# controller_v5.net
KiCad netlist of a schematic drawn in EAGLE
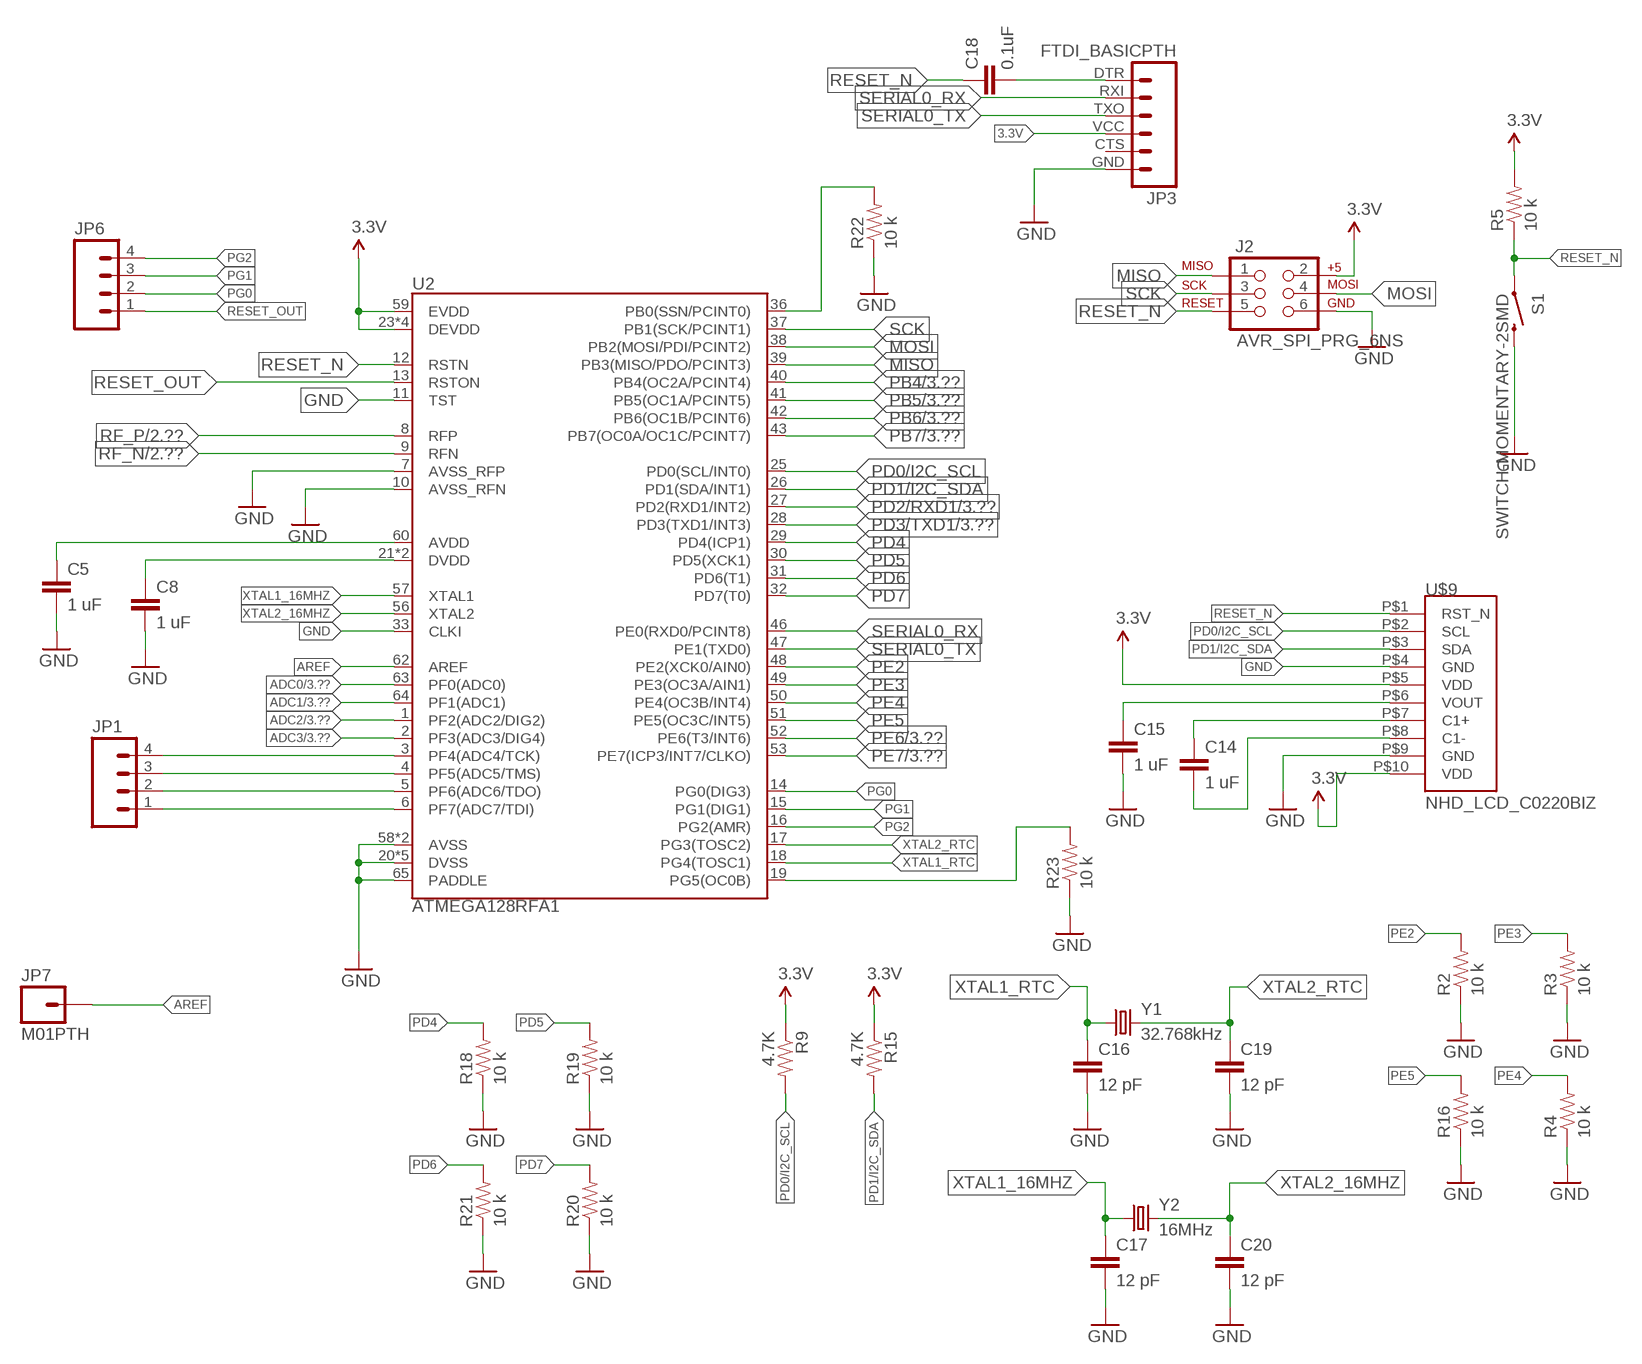
[diagram p0: schematic, sheet 1]
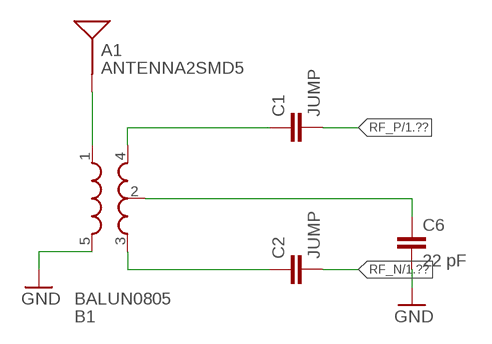
[diagram p1: schematic, sheet 2]
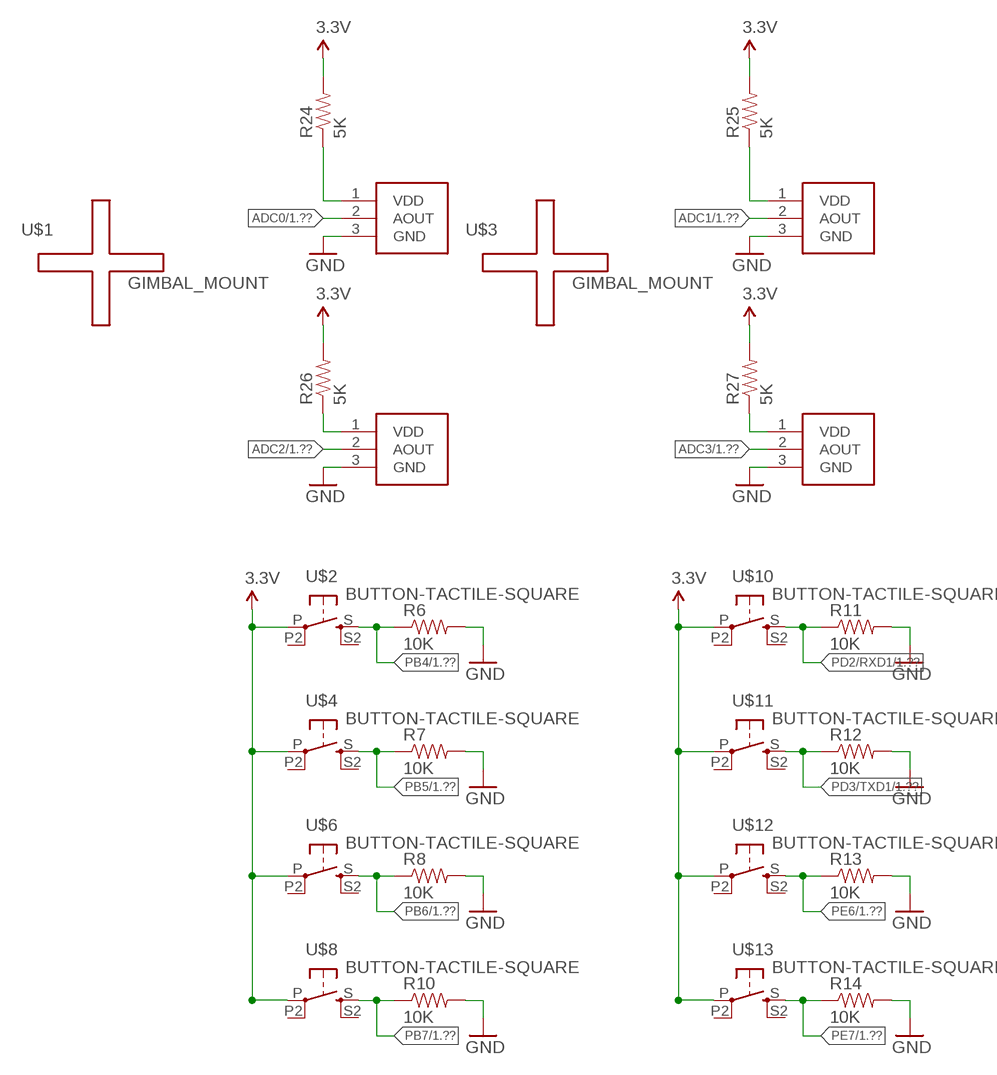
[diagram p2: schematic, sheet 3]
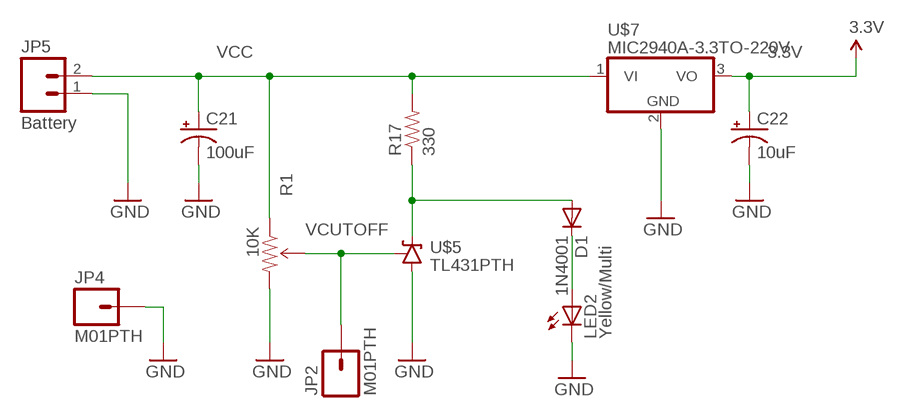
[diagram p3: schematic, sheet 4]

(export (version "E")
  (design (tool "Eeschema 10.0.6"))
  (components
    (comp (ref "C21")
      (value "100uF")
      (footprint "eagle-import:E3,5-8")
      (libsource (lib "eagle-import") (part "CPOL-USE3.5-8"))
    )
    (comp (ref "C22")
      (value "10uF")
      (footprint "eagle-import:E2,5-5")
      (libsource (lib "eagle-import") (part "CPOL-USE2.5-5"))
    )
    (comp (ref "D1")
      (value "1N4001")
      (footprint "eagle-import:DO41-10")
      (libsource (lib "eagle-import") (part "1N4004"))
    )
    (comp (ref "JP2")
      (value "M01PTH")
      (footprint "eagle-import:1X01")
      (libsource (lib "eagle-import") (part "SparkFun_M01PTH"))
    )
    (comp (ref "JP4")
      (value "M01PTH")
      (footprint "eagle-import:1X01")
      (libsource (lib "eagle-import") (part "SparkFun_M01PTH"))
    )
    (comp (ref "JP5")
      (value "Battery")
      (footprint "eagle-import:1X02")
      (libsource (lib "eagle-import") (part "M02PTH"))
    )
    (comp (ref "LED2")
      (value "Yellow/Multi")
      (footprint "eagle-import:LED5MM")
      (libsource (lib "eagle-import") (part "LED5MM"))
    )
    (comp (ref "R1")
      (value "10K")
      (footprint "eagle-import:3386U")
      (fields (field (name "CREATOR") "Brandon") (field (name "REVIEWER1") "Chris"))
      (libsource (lib "eagle-import") (part "TRIMPOT-PTH-KNOB"))
    )
    (comp (ref "R17")
      (value "330")
      (footprint "eagle-import:AXIAL-0.3")
      (libsource (lib "eagle-import") (part "SparkFun_RESISTORAXIAL-0.3"))
    )
    (comp (ref "U$5")
      (value "TL431PTH")
      (footprint "eagle-import:TO-92")
      (libsource (lib "eagle-import") (part "TL431PTH"))
    )
    (comp (ref "U$7")
      (value "MIC2940A-3.3TO-220V")
      (footprint "eagle-import:TO-220V")
      (libsource (lib "eagle-import") (part "MIC2940A-3.3TO-220V"))
    )
    (comp (ref "C5")
      (value "1 uF")
      (footprint "eagle-import:0805")
      (libsource (lib "eagle-import") (part "CAP0805"))
    )
    (comp (ref "C8")
      (value "1 uF")
      (footprint "eagle-import:0805")
      (libsource (lib "eagle-import") (part "CAP0805"))
    )
    (comp (ref "C14")
      (value "1 uF")
      (footprint "eagle-import:0805")
      (libsource (lib "eagle-import") (part "CAP0805"))
    )
    (comp (ref "C15")
      (value "1 uF")
      (footprint "eagle-import:0805")
      (libsource (lib "eagle-import") (part "CAP0805"))
    )
    (comp (ref "C16")
      (value "12 pF")
      (footprint "eagle-import:0805")
      (libsource (lib "eagle-import") (part "CAP0805"))
    )
    (comp (ref "C17")
      (value "12 pF")
      (footprint "eagle-import:0805")
      (libsource (lib "eagle-import") (part "CAP0805"))
    )
    (comp (ref "C18")
      (value "0.1uF")
      (footprint "eagle-import:0805")
      (libsource (lib "eagle-import") (part "CAP0805"))
    )
    (comp (ref "C19")
      (value "12 pF")
      (footprint "eagle-import:0805")
      (libsource (lib "eagle-import") (part "CAP0805"))
    )
    (comp (ref "C20")
      (value "12 pF")
      (footprint "eagle-import:0805")
      (libsource (lib "eagle-import") (part "CAP0805"))
    )
    (comp (ref "J2")
      (value "AVR_SPI_PRG_6NS")
      (footprint "eagle-import:2X3-NS")
      (libsource (lib "eagle-import") (part "AVR_SPI_PRG_6NS"))
    )
    (comp (ref "JP1")
      (value "M04PTH")
      (footprint "eagle-import:1X04")
      (libsource (lib "eagle-import") (part "M04PTH"))
    )
    (comp (ref "JP3")
      (value "FTDI_BASICPTH")
      (footprint "eagle-import:FTDI_BASIC")
      (libsource (lib "eagle-import") (part "FTDI_BASICPTH"))
    )
    (comp (ref "JP6")
      (value "M04PTH")
      (footprint "eagle-import:1X04")
      (libsource (lib "eagle-import") (part "M04PTH"))
    )
    (comp (ref "JP7")
      (value "M01PTH")
      (footprint "eagle-import:1X01")
      (libsource (lib "eagle-import") (part "M01PTH"))
    )
    (comp (ref "R2")
      (value "10 k")
      (footprint "eagle-import:0805")
      (libsource (lib "eagle-import") (part "RESISTOR0805-RES"))
    )
    (comp (ref "R3")
      (value "10 k")
      (footprint "eagle-import:0805")
      (libsource (lib "eagle-import") (part "RESISTOR0805-RES"))
    )
    (comp (ref "R4")
      (value "10 k")
      (footprint "eagle-import:0805")
      (libsource (lib "eagle-import") (part "RESISTOR0805-RES"))
    )
    (comp (ref "R5")
      (value "10 k")
      (footprint "eagle-import:0805")
      (libsource (lib "eagle-import") (part "RESISTOR0805-RES"))
    )
    (comp (ref "R9")
      (value "4.7K")
      (footprint "eagle-import:0805")
      (libsource (lib "eagle-import") (part "RESISTOR0805-RES"))
    )
    (comp (ref "R15")
      (value "4.7K")
      (footprint "eagle-import:0805")
      (libsource (lib "eagle-import") (part "RESISTOR0805-RES"))
    )
    (comp (ref "R16")
      (value "10 k")
      (footprint "eagle-import:0805")
      (libsource (lib "eagle-import") (part "RESISTOR0805-RES"))
    )
    (comp (ref "R18")
      (value "10 k")
      (footprint "eagle-import:0805")
      (libsource (lib "eagle-import") (part "RESISTOR0805-RES"))
    )
    (comp (ref "R19")
      (value "10 k")
      (footprint "eagle-import:0805")
      (libsource (lib "eagle-import") (part "RESISTOR0805-RES"))
    )
    (comp (ref "R20")
      (value "10 k")
      (footprint "eagle-import:0805")
      (libsource (lib "eagle-import") (part "RESISTOR0805-RES"))
    )
    (comp (ref "R21")
      (value "10 k")
      (footprint "eagle-import:0805")
      (libsource (lib "eagle-import") (part "RESISTOR0805-RES"))
    )
    (comp (ref "R22")
      (value "10 k")
      (footprint "eagle-import:0805")
      (libsource (lib "eagle-import") (part "RESISTOR0805-RES"))
    )
    (comp (ref "R23")
      (value "10 k")
      (footprint "eagle-import:0805")
      (libsource (lib "eagle-import") (part "RESISTOR0805-RES"))
    )
    (comp (ref "S1")
      (value "SWITCH-MOMENTARY-2SMD")
      (footprint "eagle-import:TACTILE_SWITCH_SMD")
      (libsource (lib "eagle-import") (part "SWITCH-MOMENTARY-2SMD"))
    )
    (comp (ref "U$9")
      (value "NHD_LCD_C0220BIZ")
      (footprint "eagle-import:1X08-2MMPTH-LCD")
      (libsource (lib "eagle-import") (part "NHD_LCD_C0220BIZ"))
    )
    (comp (ref "U2")
      (value "ATMEGA128RFA1")
      (footprint "eagle-import:QFN-64")
      (libsource (lib "eagle-import") (part "ATMEGA128RFA1"))
    )
    (comp (ref "Y1")
      (value "32.768kHz")
      (footprint "eagle-import:CRYSTAL-32KHZ-SMD")
      (libsource (lib "eagle-import") (part "CRYSTAL32-SMD"))
    )
    (comp (ref "Y2")
      (value "16MHz")
      (footprint "eagle-import:CRYSTAL-SMD-5X3")
      (libsource (lib "eagle-import") (part "CRYSTAL5X3"))
    )
    (comp (ref "J3")
      (value "GIMBAL_3PIN")
      (footprint "eagle-import:JST-3-PTH")
      (libsource (lib "eagle-import") (part "GIMBAL_3PIN"))
    )
    (comp (ref "J4")
      (value "GIMBAL_3PIN")
      (footprint "eagle-import:JST-3-PTH")
      (libsource (lib "eagle-import") (part "GIMBAL_3PIN"))
    )
    (comp (ref "J5")
      (value "GIMBAL_3PIN")
      (footprint "eagle-import:JST-3-PTH")
      (libsource (lib "eagle-import") (part "GIMBAL_3PIN"))
    )
    (comp (ref "J6")
      (value "GIMBAL_3PIN")
      (footprint "eagle-import:JST-3-PTH")
      (libsource (lib "eagle-import") (part "GIMBAL_3PIN"))
    )
    (comp (ref "R6")
      (value "10K")
      (footprint "eagle-import:0805")
      (libsource (lib "eagle-import") (part "RESISTOR0805-RES"))
    )
    (comp (ref "R7")
      (value "10K")
      (footprint "eagle-import:0805")
      (libsource (lib "eagle-import") (part "RESISTOR0805-RES"))
    )
    (comp (ref "R8")
      (value "10K")
      (footprint "eagle-import:0805")
      (libsource (lib "eagle-import") (part "RESISTOR0805-RES"))
    )
    (comp (ref "R10")
      (value "10K")
      (footprint "eagle-import:0805")
      (libsource (lib "eagle-import") (part "RESISTOR0805-RES"))
    )
    (comp (ref "R11")
      (value "10K")
      (footprint "eagle-import:0805")
      (libsource (lib "eagle-import") (part "RESISTOR0805-RES"))
    )
    (comp (ref "R12")
      (value "10K")
      (footprint "eagle-import:0805")
      (libsource (lib "eagle-import") (part "RESISTOR0805-RES"))
    )
    (comp (ref "R13")
      (value "10K")
      (footprint "eagle-import:0805")
      (libsource (lib "eagle-import") (part "RESISTOR0805-RES"))
    )
    (comp (ref "R14")
      (value "10K")
      (footprint "eagle-import:0805")
      (libsource (lib "eagle-import") (part "RESISTOR0805-RES"))
    )
    (comp (ref "R24")
      (value "5K")
      (footprint "eagle-import:0805")
      (libsource (lib "eagle-import") (part "RESISTOR0805-RES"))
    )
    (comp (ref "R25")
      (value "5K")
      (footprint "eagle-import:0805")
      (libsource (lib "eagle-import") (part "RESISTOR0805-RES"))
    )
    (comp (ref "R26")
      (value "5K")
      (footprint "eagle-import:0805")
      (libsource (lib "eagle-import") (part "RESISTOR0805-RES"))
    )
    (comp (ref "R27")
      (value "5K")
      (footprint "eagle-import:0805")
      (libsource (lib "eagle-import") (part "RESISTOR0805-RES"))
    )
    (comp (ref "U$1")
      (value "GIMBAL_MOUNT")
      (footprint "eagle-import:GIMBAL_FOOTPRINT")
      (libsource (lib "eagle-import") (part "GIMBAL_MOUNT"))
    )
    (comp (ref "U$2")
      (value "BUTTON-TACTILE-SQUARE")
      (footprint "eagle-import:BUTTON-TACTILE-SQUARE-ADAFRUIT1010")
      (libsource (lib "eagle-import") (part "BUTTON-TACTILE-SQUARE"))
    )
    (comp (ref "U$3")
      (value "GIMBAL_MOUNT")
      (footprint "eagle-import:GIMBAL_FOOTPRINT")
      (libsource (lib "eagle-import") (part "GIMBAL_MOUNT"))
    )
    (comp (ref "U$4")
      (value "BUTTON-TACTILE-SQUARE")
      (footprint "eagle-import:BUTTON-TACTILE-SQUARE-ADAFRUIT1010")
      (libsource (lib "eagle-import") (part "BUTTON-TACTILE-SQUARE"))
    )
    (comp (ref "U$6")
      (value "BUTTON-TACTILE-SQUARE")
      (footprint "eagle-import:BUTTON-TACTILE-SQUARE-ADAFRUIT1010")
      (libsource (lib "eagle-import") (part "BUTTON-TACTILE-SQUARE"))
    )
    (comp (ref "U$8")
      (value "BUTTON-TACTILE-SQUARE")
      (footprint "eagle-import:BUTTON-TACTILE-SQUARE-ADAFRUIT1010")
      (libsource (lib "eagle-import") (part "BUTTON-TACTILE-SQUARE"))
    )
    (comp (ref "U$10")
      (value "BUTTON-TACTILE-SQUARE")
      (footprint "eagle-import:BUTTON-TACTILE-SQUARE-ADAFRUIT1010")
      (libsource (lib "eagle-import") (part "BUTTON-TACTILE-SQUARE"))
    )
    (comp (ref "U$11")
      (value "BUTTON-TACTILE-SQUARE")
      (footprint "eagle-import:BUTTON-TACTILE-SQUARE-ADAFRUIT1010")
      (libsource (lib "eagle-import") (part "BUTTON-TACTILE-SQUARE"))
    )
    (comp (ref "U$12")
      (value "BUTTON-TACTILE-SQUARE")
      (footprint "eagle-import:BUTTON-TACTILE-SQUARE-ADAFRUIT1010")
      (libsource (lib "eagle-import") (part "BUTTON-TACTILE-SQUARE"))
    )
    (comp (ref "U$13")
      (value "BUTTON-TACTILE-SQUARE")
      (footprint "eagle-import:BUTTON-TACTILE-SQUARE-ADAFRUIT1010")
      (libsource (lib "eagle-import") (part "BUTTON-TACTILE-SQUARE"))
    )
    (comp (ref "A1")
      (value "ANTENNA2SMD5")
      (footprint "eagle-import:ANTENNA-CHIP5")
      (libsource (lib "eagle-import") (part "ANTENNA2SMD5"))
    )
    (comp (ref "B1")
      (value "BALUN0805")
      (footprint "eagle-import:BALUN")
      (libsource (lib "eagle-import") (part "BALUN0805"))
    )
    (comp (ref "C1")
      (value "JUMP")
      (footprint "eagle-import:0805")
      (libsource (lib "eagle-import") (part "CAP0805"))
    )
    (comp (ref "C2")
      (value "JUMP")
      (footprint "eagle-import:0805")
      (libsource (lib "eagle-import") (part "CAP0805"))
    )
    (comp (ref "C6")
      (value "22 pF")
      (footprint "eagle-import:0805")
      (libsource (lib "eagle-import") (part "CAP0805"))
    )
  )
  (nets
    (net (code "1") (name "3.3V") (class "Default")
      (node (ref "C22") (pin "+") (pinfunction "+_+") (pintype "passive"))
      (node (ref "J2") (pin "2") (pinfunction "2_2") (pintype "passive"))
      (node (ref "JP3") (pin "VCC") (pinfunction "4_VCC") (pintype "passive"))
      (node (ref "R15") (pin "1") (pinfunction "1_1") (pintype "passive"))
      (node (ref "R24") (pin "2") (pinfunction "2_2") (pintype "passive"))
      (node (ref "R25") (pin "2") (pinfunction "2_2") (pintype "passive"))
      (node (ref "R26") (pin "2") (pinfunction "2_2") (pintype "passive"))
      (node (ref "R27") (pin "2") (pinfunction "2_2") (pintype "passive"))
      (node (ref "R5") (pin "2") (pinfunction "2_2") (pintype "passive"))
      (node (ref "R9") (pin "1") (pinfunction "1_1") (pintype "passive"))
      (node (ref "U$10") (pin "P") (pinfunction "P_P") (pintype "passive"))
      (node (ref "U$11") (pin "P") (pinfunction "P_P") (pintype "passive"))
      (node (ref "U$12") (pin "P") (pinfunction "P_P") (pintype "passive"))
      (node (ref "U$13") (pin "P") (pinfunction "P_P") (pintype "passive"))
      (node (ref "U$2") (pin "P") (pinfunction "P_P") (pintype "passive"))
      (node (ref "U$4") (pin "P") (pinfunction "P_P") (pintype "passive"))
      (node (ref "U$6") (pin "P") (pinfunction "P_P") (pintype "passive"))
      (node (ref "U$7") (pin "3") (pinfunction "VO_3") (pintype "passive"))
      (node (ref "U$8") (pin "P") (pinfunction "P_P") (pintype "passive"))
      (node (ref "U$9") (pin "P$10") (pinfunction "VDD_P$10") (pintype "bidirectional"))
      (node (ref "U$9") (pin "P$5") (pinfunction "VDD_P$5") (pintype "bidirectional"))
      (node (ref "U2") (pin "23") (pinfunction "DEVDD_23") (pintype "bidirectional"))
      (node (ref "U2") (pin "34") (pinfunction "DEVDD_34") (pintype "bidirectional"))
      (node (ref "U2") (pin "44") (pinfunction "DEVDD_44") (pintype "bidirectional"))
      (node (ref "U2") (pin "54") (pinfunction "DEVDD_54") (pintype "bidirectional"))
      (node (ref "U2") (pin "59") (pinfunction "EVDD_59") (pintype "bidirectional"))
    )
    (net (code "2") (name "ADC0") (class "Default")
      (node (ref "J6") (pin "2") (pinfunction "AOUT_2") (pintype "bidirectional"))
      (node (ref "U2") (pin "63") (pinfunction "PF0(ADC0)_63") (pintype "bidirectional"))
    )
    (net (code "3") (name "ADC1") (class "Default")
      (node (ref "J3") (pin "2") (pinfunction "AOUT_2") (pintype "bidirectional"))
      (node (ref "U2") (pin "64") (pinfunction "PF1(ADC1)_64") (pintype "bidirectional"))
    )
    (net (code "4") (name "ADC2") (class "Default")
      (node (ref "J5") (pin "2") (pinfunction "AOUT_2") (pintype "bidirectional"))
      (node (ref "U2") (pin "1") (pinfunction "PF2(ADC2/DIG2)_1") (pintype "bidirectional"))
    )
    (net (code "5") (name "ADC3") (class "Default")
      (node (ref "J4") (pin "2") (pinfunction "AOUT_2") (pintype "bidirectional"))
      (node (ref "U2") (pin "2") (pinfunction "PF3(ADC3/DIG4)_2") (pintype "bidirectional"))
    )
    (net (code "6") (name "AREF") (class "Default")
      (node (ref "JP7") (pin "1") (pinfunction "1_1") (pintype "passive"))
      (node (ref "U2") (pin "62") (pinfunction "AREF_62") (pintype "bidirectional"))
    )
    (net (code "7") (name "GND") (class "Default")
      (node (ref "B1") (pin "5") (pinfunction "GND_5") (pintype "bidirectional"))
      (node (ref "C15") (pin "2") (pinfunction "2_2") (pintype "passive"))
      (node (ref "C16") (pin "2") (pinfunction "2_2") (pintype "passive"))
      (node (ref "C17") (pin "2") (pinfunction "2_2") (pintype "passive"))
      (node (ref "C19") (pin "2") (pinfunction "2_2") (pintype "passive"))
      (node (ref "C20") (pin "2") (pinfunction "2_2") (pintype "passive"))
      (node (ref "C21") (pin "-") (pinfunction "-_-") (pintype "passive"))
      (node (ref "C22") (pin "-") (pinfunction "-_-") (pintype "passive"))
      (node (ref "C5") (pin "2") (pinfunction "2_2") (pintype "passive"))
      (node (ref "C6") (pin "2") (pinfunction "2_2") (pintype "passive"))
      (node (ref "C8") (pin "2") (pinfunction "2_2") (pintype "passive"))
      (node (ref "J2") (pin "6") (pinfunction "6_6") (pintype "passive"))
      (node (ref "J3") (pin "3") (pinfunction "GND_3") (pintype "power_in"))
      (node (ref "J4") (pin "3") (pinfunction "GND_3") (pintype "power_in"))
      (node (ref "J5") (pin "3") (pinfunction "GND_3") (pintype "power_in"))
      (node (ref "J6") (pin "3") (pinfunction "GND_3") (pintype "power_in"))
      (node (ref "JP3") (pin "GND") (pinfunction "6_GND") (pintype "passive"))
      (node (ref "JP4") (pin "1") (pinfunction "1_1") (pintype "passive"))
      (node (ref "JP5") (pin "1") (pinfunction "1_1") (pintype "passive"))
      (node (ref "LED2") (pin "K") (pinfunction "C_K") (pintype "passive"))
      (node (ref "R1") (pin "3") (pinfunction "CW_3") (pintype "passive"))
      (node (ref "R10") (pin "2") (pinfunction "2_2") (pintype "passive"))
      (node (ref "R11") (pin "2") (pinfunction "2_2") (pintype "passive"))
      (node (ref "R12") (pin "2") (pinfunction "2_2") (pintype "passive"))
      (node (ref "R13") (pin "2") (pinfunction "2_2") (pintype "passive"))
      (node (ref "R14") (pin "2") (pinfunction "2_2") (pintype "passive"))
      (node (ref "R16") (pin "1") (pinfunction "1_1") (pintype "passive"))
      (node (ref "R18") (pin "1") (pinfunction "1_1") (pintype "passive"))
      (node (ref "R19") (pin "1") (pinfunction "1_1") (pintype "passive"))
      (node (ref "R2") (pin "1") (pinfunction "1_1") (pintype "passive"))
      (node (ref "R20") (pin "1") (pinfunction "1_1") (pintype "passive"))
      (node (ref "R21") (pin "1") (pinfunction "1_1") (pintype "passive"))
      (node (ref "R22") (pin "1") (pinfunction "1_1") (pintype "passive"))
      (node (ref "R23") (pin "1") (pinfunction "1_1") (pintype "passive"))
      (node (ref "R3") (pin "1") (pinfunction "1_1") (pintype "passive"))
      (node (ref "R4") (pin "1") (pinfunction "1_1") (pintype "passive"))
      (node (ref "R6") (pin "2") (pinfunction "2_2") (pintype "passive"))
      (node (ref "R7") (pin "2") (pinfunction "2_2") (pintype "passive"))
      (node (ref "R8") (pin "2") (pinfunction "2_2") (pintype "passive"))
      (node (ref "S1") (pin "3") (pinfunction "2_3") (pintype "passive"))
      (node (ref "U$5") (pin "2") (pinfunction "A_2") (pintype "passive"))
      (node (ref "U$7") (pin "2") (pinfunction "GND_2") (pintype "passive"))
      (node (ref "U$9") (pin "P$4") (pinfunction "GND_P$4") (pintype "bidirectional"))
      (node (ref "U$9") (pin "P$9") (pinfunction "GND_P$9") (pintype "bidirectional"))
      (node (ref "U2") (pin "10") (pinfunction "AVSS_RFN_10") (pintype "bidirectional"))
      (node (ref "U2") (pin "11") (pinfunction "TST_11") (pintype "bidirectional"))
      (node (ref "U2") (pin "20") (pinfunction "DVSS_20") (pintype "bidirectional"))
      (node (ref "U2") (pin "24") (pinfunction "DVSS_24") (pintype "bidirectional"))
      (node (ref "U2") (pin "33") (pinfunction "CLKI_33") (pintype "bidirectional"))
      (node (ref "U2") (pin "35") (pinfunction "DVSS_35") (pintype "bidirectional"))
      (node (ref "U2") (pin "45") (pinfunction "DVSS_45") (pintype "bidirectional"))
      (node (ref "U2") (pin "55") (pinfunction "DVSS_55") (pintype "bidirectional"))
      (node (ref "U2") (pin "58") (pinfunction "AVSS_58") (pintype "bidirectional"))
      (node (ref "U2") (pin "61") (pinfunction "AVSS_61") (pintype "bidirectional"))
      (node (ref "U2") (pin "65") (pinfunction "PADDLE_65") (pintype "bidirectional"))
      (node (ref "U2") (pin "7") (pinfunction "AVSS_RFP_7") (pintype "bidirectional"))
    )
    (net (code "8") (name "MISO") (class "Default")
      (node (ref "J2") (pin "1") (pinfunction "1_1") (pintype "passive"))
      (node (ref "U2") (pin "39") (pinfunction "PB3(MISO/PDO/PCINT3)_39") (pintype "bidirectional"))
    )
    (net (code "9") (name "MOSI") (class "Default")
      (node (ref "J2") (pin "4") (pinfunction "4_4") (pintype "passive"))
      (node (ref "U2") (pin "38") (pinfunction "PB2(MOSI/PDI/PCINT2)_38") (pintype "bidirectional"))
    )
    (net (code "10") (name "Net-(A1-SIGNAL)") (class "Default")
      (node (ref "A1") (pin "FEED") (pinfunction "SIGNAL_FEED") (pintype "bidirectional"))
      (node (ref "B1") (pin "1") (pinfunction "IN_1") (pintype "bidirectional"))
    )
    (net (code "11") (name "Net-(B1-GND-Pad2)") (class "Default")
      (node (ref "B1") (pin "2") (pinfunction "GND_2") (pintype "bidirectional"))
      (node (ref "C6") (pin "1") (pinfunction "1_1") (pintype "passive"))
    )
    (net (code "12") (name "Net-(B1-OUT1)") (class "Default")
      (node (ref "B1") (pin "4") (pinfunction "OUT1_4") (pintype "bidirectional"))
      (node (ref "C1") (pin "1") (pinfunction "1_1") (pintype "passive"))
    )
    (net (code "13") (name "Net-(B1-OUT2)") (class "Default")
      (node (ref "B1") (pin "3") (pinfunction "OUT2_3") (pintype "bidirectional"))
      (node (ref "C2") (pin "1") (pinfunction "1_1") (pintype "passive"))
    )
    (net (code "14") (name "Net-(C8-Pad1)") (class "Default")
      (node (ref "C8") (pin "1") (pinfunction "1_1") (pintype "passive"))
      (node (ref "U2") (pin "21") (pinfunction "DVDD_21") (pintype "bidirectional"))
      (node (ref "U2") (pin "22") (pinfunction "DVDD_22") (pintype "bidirectional"))
    )
    (net (code "15") (name "Net-(D1-PadC)") (class "Default")
      (node (ref "D1") (pin "C") (pinfunction "C_C") (pintype "passive"))
      (node (ref "LED2") (pin "A") (pinfunction "A_A") (pintype "passive"))
    )
    (net (code "16") (name "Net-(J3-VDD)") (class "Default")
      (node (ref "J3") (pin "1") (pinfunction "VDD_1") (pintype "power_in"))
      (node (ref "R25") (pin "1") (pinfunction "1_1") (pintype "passive"))
    )
    (net (code "17") (name "Net-(J4-VDD)") (class "Default")
      (node (ref "J4") (pin "1") (pinfunction "VDD_1") (pintype "power_in"))
      (node (ref "R27") (pin "1") (pinfunction "1_1") (pintype "passive"))
    )
    (net (code "18") (name "Net-(J5-VDD)") (class "Default")
      (node (ref "J5") (pin "1") (pinfunction "VDD_1") (pintype "power_in"))
      (node (ref "R26") (pin "1") (pinfunction "1_1") (pintype "passive"))
    )
    (net (code "19") (name "Net-(J6-VDD)") (class "Default")
      (node (ref "J6") (pin "1") (pinfunction "VDD_1") (pintype "power_in"))
      (node (ref "R24") (pin "1") (pinfunction "1_1") (pintype "passive"))
    )
    (net (code "20") (name "Net-(JP3-1)") (class "Default")
      (node (ref "C18") (pin "2") (pinfunction "2_2") (pintype "passive"))
      (node (ref "JP3") (pin "DTR") (pinfunction "1_DTR") (pintype "passive"))
    )
    (net (code "21") (name "Net-(R17-1)") (class "Default")
      (node (ref "D1") (pin "A") (pinfunction "A_A") (pintype "passive"))
      (node (ref "R17") (pin "P$1") (pinfunction "1_P$1") (pintype "passive"))
      (node (ref "U$5") (pin "3") (pinfunction "C_3") (pintype "passive"))
    )
    (net (code "22") (name "Net-(U$9-C1+)") (class "Default")
      (node (ref "C14") (pin "1") (pinfunction "1_1") (pintype "passive"))
      (node (ref "U$9") (pin "P$7") (pinfunction "C1+_P$7") (pintype "bidirectional"))
    )
    (net (code "23") (name "Net-(U$9-C1-)") (class "Default")
      (node (ref "C14") (pin "2") (pinfunction "2_2") (pintype "passive"))
      (node (ref "U$9") (pin "P$8") (pinfunction "C1-_P$8") (pintype "bidirectional"))
    )
    (net (code "24") (name "Net-(U$9-VOUT)") (class "Default")
      (node (ref "C15") (pin "1") (pinfunction "1_1") (pintype "passive"))
      (node (ref "U$9") (pin "P$6") (pinfunction "VOUT_P$6") (pintype "bidirectional"))
    )
    (net (code "25") (name "Net-(U2-AVDD)") (class "Default")
      (node (ref "C5") (pin "1") (pinfunction "1_1") (pintype "passive"))
      (node (ref "U2") (pin "60") (pinfunction "AVDD_60") (pintype "bidirectional"))
    )
    (net (code "26") (name "Net-(U2-PB0(SSN{slash}PCINT0))") (class "Default")
      (node (ref "R22") (pin "2") (pinfunction "2_2") (pintype "passive"))
      (node (ref "U2") (pin "36") (pinfunction "PB0(SSN/PCINT0)_36") (pintype "bidirectional"))
    )
    (net (code "27") (name "Net-(U2-PF4(ADC4{slash}TCK))") (class "Default")
      (node (ref "JP1") (pin "4") (pinfunction "4_4") (pintype "passive"))
      (node (ref "U2") (pin "3") (pinfunction "PF4(ADC4/TCK)_3") (pintype "bidirectional"))
    )
    (net (code "28") (name "Net-(U2-PF5(ADC5{slash}TMS))") (class "Default")
      (node (ref "JP1") (pin "3") (pinfunction "3_3") (pintype "passive"))
      (node (ref "U2") (pin "4") (pinfunction "PF5(ADC5/TMS)_4") (pintype "bidirectional"))
    )
    (net (code "29") (name "Net-(U2-PF6(ADC6{slash}TDO))") (class "Default")
      (node (ref "JP1") (pin "2") (pinfunction "2_2") (pintype "passive"))
      (node (ref "U2") (pin "5") (pinfunction "PF6(ADC6/TDO)_5") (pintype "bidirectional"))
    )
    (net (code "30") (name "Net-(U2-PF7(ADC7{slash}TDI))") (class "Default")
      (node (ref "JP1") (pin "1") (pinfunction "1_1") (pintype "passive"))
      (node (ref "U2") (pin "6") (pinfunction "PF7(ADC7/TDI)_6") (pintype "bidirectional"))
    )
    (net (code "31") (name "Net-(U2-PG5(OC0B))") (class "Default")
      (node (ref "R23") (pin "2") (pinfunction "2_2") (pintype "passive"))
      (node (ref "U2") (pin "19") (pinfunction "PG5(OC0B)_19") (pintype "bidirectional"))
    )
    (net (code "32") (name "PB4") (class "Default")
      (node (ref "R6") (pin "1") (pinfunction "1_1") (pintype "passive"))
      (node (ref "U$2") (pin "S") (pinfunction "S_S") (pintype "passive"))
      (node (ref "U2") (pin "40") (pinfunction "PB4(OC2A/PCINT4)_40") (pintype "bidirectional"))
    )
    (net (code "33") (name "PB5") (class "Default")
      (node (ref "R7") (pin "1") (pinfunction "1_1") (pintype "passive"))
      (node (ref "U$4") (pin "S") (pinfunction "S_S") (pintype "passive"))
      (node (ref "U2") (pin "41") (pinfunction "PB5(OC1A/PCINT5)_41") (pintype "bidirectional"))
    )
    (net (code "34") (name "PB6") (class "Default")
      (node (ref "R8") (pin "1") (pinfunction "1_1") (pintype "passive"))
      (node (ref "U$6") (pin "S") (pinfunction "S_S") (pintype "passive"))
      (node (ref "U2") (pin "42") (pinfunction "PB6(OC1B/PCINT6)_42") (pintype "bidirectional"))
    )
    (net (code "35") (name "PB7") (class "Default")
      (node (ref "R10") (pin "1") (pinfunction "1_1") (pintype "passive"))
      (node (ref "U$8") (pin "S") (pinfunction "S_S") (pintype "passive"))
      (node (ref "U2") (pin "43") (pinfunction "PB7(OC0A/OC1C/PCINT7)_43") (pintype "bidirectional"))
    )
    (net (code "36") (name "PD0{slash}I2C_SCL") (class "Default")
      (node (ref "R9") (pin "2") (pinfunction "2_2") (pintype "passive"))
      (node (ref "U$9") (pin "P$2") (pinfunction "SCL_P$2") (pintype "bidirectional"))
      (node (ref "U2") (pin "25") (pinfunction "PD0(SCL/INT0)_25") (pintype "bidirectional"))
    )
    (net (code "37") (name "PD1{slash}I2C_SDA") (class "Default")
      (node (ref "R15") (pin "2") (pinfunction "2_2") (pintype "passive"))
      (node (ref "U$9") (pin "P$3") (pinfunction "SDA_P$3") (pintype "bidirectional"))
      (node (ref "U2") (pin "26") (pinfunction "PD1(SDA/INT1)_26") (pintype "bidirectional"))
    )
    (net (code "38") (name "PD2{slash}RXD1") (class "Default")
      (node (ref "R11") (pin "1") (pinfunction "1_1") (pintype "passive"))
      (node (ref "U$10") (pin "S") (pinfunction "S_S") (pintype "passive"))
      (node (ref "U2") (pin "27") (pinfunction "PD2(RXD1/INT2)_27") (pintype "bidirectional"))
    )
    (net (code "39") (name "PD3{slash}TXD1") (class "Default")
      (node (ref "R12") (pin "1") (pinfunction "1_1") (pintype "passive"))
      (node (ref "U$11") (pin "S") (pinfunction "S_S") (pintype "passive"))
      (node (ref "U2") (pin "28") (pinfunction "PD3(TXD1/INT3)_28") (pintype "bidirectional"))
    )
    (net (code "40") (name "PD4") (class "Default")
      (node (ref "R18") (pin "2") (pinfunction "2_2") (pintype "passive"))
      (node (ref "U2") (pin "29") (pinfunction "PD4(ICP1)_29") (pintype "bidirectional"))
    )
    (net (code "41") (name "PD5") (class "Default")
      (node (ref "R19") (pin "2") (pinfunction "2_2") (pintype "passive"))
      (node (ref "U2") (pin "30") (pinfunction "PD5(XCK1)_30") (pintype "bidirectional"))
    )
    (net (code "42") (name "PD6") (class "Default")
      (node (ref "R21") (pin "2") (pinfunction "2_2") (pintype "passive"))
      (node (ref "U2") (pin "31") (pinfunction "PD6(T1)_31") (pintype "bidirectional"))
    )
    (net (code "43") (name "PD7") (class "Default")
      (node (ref "R20") (pin "2") (pinfunction "2_2") (pintype "passive"))
      (node (ref "U2") (pin "32") (pinfunction "PD7(T0)_32") (pintype "bidirectional"))
    )
    (net (code "44") (name "PE2") (class "Default")
      (node (ref "R2") (pin "2") (pinfunction "2_2") (pintype "passive"))
      (node (ref "U2") (pin "48") (pinfunction "PE2(XCK0/AIN0)_48") (pintype "bidirectional"))
    )
    (net (code "45") (name "PE3") (class "Default")
      (node (ref "R3") (pin "2") (pinfunction "2_2") (pintype "passive"))
      (node (ref "U2") (pin "49") (pinfunction "PE3(OC3A/AIN1)_49") (pintype "bidirectional"))
    )
    (net (code "46") (name "PE4") (class "Default")
      (node (ref "R4") (pin "2") (pinfunction "2_2") (pintype "passive"))
      (node (ref "U2") (pin "50") (pinfunction "PE4(OC3B/INT4)_50") (pintype "bidirectional"))
    )
    (net (code "47") (name "PE5") (class "Default")
      (node (ref "R16") (pin "2") (pinfunction "2_2") (pintype "passive"))
      (node (ref "U2") (pin "51") (pinfunction "PE5(OC3C/INT5)_51") (pintype "bidirectional"))
    )
    (net (code "48") (name "PE6") (class "Default")
      (node (ref "R13") (pin "1") (pinfunction "1_1") (pintype "passive"))
      (node (ref "U$12") (pin "S") (pinfunction "S_S") (pintype "passive"))
      (node (ref "U2") (pin "52") (pinfunction "PE6(T3/INT6)_52") (pintype "bidirectional"))
    )
    (net (code "49") (name "PE7") (class "Default")
      (node (ref "R14") (pin "1") (pinfunction "1_1") (pintype "passive"))
      (node (ref "U$13") (pin "S") (pinfunction "S_S") (pintype "passive"))
      (node (ref "U2") (pin "53") (pinfunction "PE7(ICP3/INT7/CLKO)_53") (pintype "bidirectional"))
    )
    (net (code "50") (name "PG0") (class "Default")
      (node (ref "JP6") (pin "2") (pinfunction "2_2") (pintype "passive"))
      (node (ref "U2") (pin "14") (pinfunction "PG0(DIG3)_14") (pintype "bidirectional"))
    )
    (net (code "51") (name "PG1") (class "Default")
      (node (ref "JP6") (pin "3") (pinfunction "3_3") (pintype "passive"))
      (node (ref "U2") (pin "15") (pinfunction "PG1(DIG1)_15") (pintype "bidirectional"))
    )
    (net (code "52") (name "PG2") (class "Default")
      (node (ref "JP6") (pin "4") (pinfunction "4_4") (pintype "passive"))
      (node (ref "U2") (pin "16") (pinfunction "PG2(AMR)_16") (pintype "bidirectional"))
    )
    (net (code "53") (name "RESET_N") (class "Default")
      (node (ref "C18") (pin "1") (pinfunction "1_1") (pintype "passive"))
      (node (ref "J2") (pin "5") (pinfunction "5_5") (pintype "passive"))
      (node (ref "R5") (pin "1") (pinfunction "1_1") (pintype "passive"))
      (node (ref "S1") (pin "1") (pinfunction "1_1") (pintype "passive"))
      (node (ref "U$9") (pin "P$1") (pinfunction "RST_N_P$1") (pintype "bidirectional"))
      (node (ref "U2") (pin "12") (pinfunction "RSTN_12") (pintype "bidirectional"))
    )
    (net (code "54") (name "RESET_OUT") (class "Default")
      (node (ref "JP6") (pin "1") (pinfunction "1_1") (pintype "passive"))
      (node (ref "U2") (pin "13") (pinfunction "RSTON_13") (pintype "bidirectional"))
    )
    (net (code "55") (name "RF_N") (class "Default")
      (node (ref "C2") (pin "2") (pinfunction "2_2") (pintype "passive"))
      (node (ref "U2") (pin "9") (pinfunction "RFN_9") (pintype "bidirectional"))
    )
    (net (code "56") (name "RF_P") (class "Default")
      (node (ref "C1") (pin "2") (pinfunction "2_2") (pintype "passive"))
      (node (ref "U2") (pin "8") (pinfunction "RFP_8") (pintype "bidirectional"))
    )
    (net (code "57") (name "SCK") (class "Default")
      (node (ref "J2") (pin "3") (pinfunction "3_3") (pintype "passive"))
      (node (ref "U2") (pin "37") (pinfunction "PB1(SCK/PCINT1)_37") (pintype "bidirectional"))
    )
    (net (code "58") (name "SERIAL0_RX") (class "Default")
      (node (ref "JP3") (pin "RXI") (pinfunction "2_RXI") (pintype "passive"))
      (node (ref "U2") (pin "46") (pinfunction "PE0(RXD0/PCINT8)_46") (pintype "bidirectional"))
    )
    (net (code "59") (name "SERIAL0_TX") (class "Default")
      (node (ref "JP3") (pin "TXO") (pinfunction "3_TXO") (pintype "passive"))
      (node (ref "U2") (pin "47") (pinfunction "PE1(TXD0)_47") (pintype "bidirectional"))
    )
    (net (code "60") (name "VCC") (class "Default")
      (node (ref "C21") (pin "+") (pinfunction "+_+") (pintype "passive"))
      (node (ref "JP5") (pin "2") (pinfunction "2_2") (pintype "passive"))
      (node (ref "R1") (pin "1") (pinfunction "CCW_1") (pintype "passive"))
      (node (ref "R17") (pin "P$2") (pinfunction "2_P$2") (pintype "passive"))
      (node (ref "U$7") (pin "1") (pinfunction "VI_1") (pintype "input"))
    )
    (net (code "61") (name "VCUTOFF") (class "Default")
      (node (ref "JP2") (pin "1") (pinfunction "1_1") (pintype "passive"))
      (node (ref "R1") (pin "2") (pinfunction "WIPER_2") (pintype "passive"))
      (node (ref "U$5") (pin "1") (pinfunction "R_1") (pintype "bidirectional"))
    )
    (net (code "62") (name "XTAL1_16MHZ") (class "Default")
      (node (ref "C17") (pin "1") (pinfunction "1_1") (pintype "passive"))
      (node (ref "U2") (pin "57") (pinfunction "XTAL1_57") (pintype "bidirectional"))
      (node (ref "Y2") (pin "1") (pinfunction "1_1") (pintype "passive"))
    )
    (net (code "63") (name "XTAL1_RTC") (class "Default")
      (node (ref "C16") (pin "1") (pinfunction "1_1") (pintype "passive"))
      (node (ref "U2") (pin "18") (pinfunction "PG4(TOSC1)_18") (pintype "bidirectional"))
      (node (ref "Y1") (pin "X1") (pinfunction "1_X1") (pintype "passive"))
    )
    (net (code "64") (name "XTAL2_16MHZ") (class "Default")
      (node (ref "C20") (pin "1") (pinfunction "1_1") (pintype "passive"))
      (node (ref "U2") (pin "56") (pinfunction "XTAL2_56") (pintype "bidirectional"))
      (node (ref "Y2") (pin "3") (pinfunction "2_3") (pintype "passive"))
    )
    (net (code "65") (name "XTAL2_RTC") (class "Default")
      (node (ref "C19") (pin "1") (pinfunction "1_1") (pintype "passive"))
      (node (ref "U2") (pin "17") (pinfunction "PG3(TOSC2)_17") (pintype "bidirectional"))
      (node (ref "Y1") (pin "X2") (pinfunction "2_X2") (pintype "passive"))
    )
    (net (code "66") (name "unconnected-(JP3-5-PadCTS)") (class "Default")
      (node (ref "JP3") (pin "CTS") (pinfunction "5_CTS") (pintype "passive"))
    )
    (net (code "67") (name "unconnected-(U$2-P1-PadP2)") (class "Default")
      (node (ref "U$2") (pin "P2") (pinfunction "P1_P2") (pintype "passive"))
    )
    (net (code "68") (name "unconnected-(U$2-S1-PadS2)") (class "Default")
      (node (ref "U$2") (pin "S2") (pinfunction "S1_S2") (pintype "passive"))
    )
    (net (code "69") (name "unconnected-(U$4-P1-PadP2)") (class "Default")
      (node (ref "U$4") (pin "P2") (pinfunction "P1_P2") (pintype "passive"))
    )
    (net (code "70") (name "unconnected-(U$4-S1-PadS2)") (class "Default")
      (node (ref "U$4") (pin "S2") (pinfunction "S1_S2") (pintype "passive"))
    )
    (net (code "71") (name "unconnected-(U$6-P1-PadP2)") (class "Default")
      (node (ref "U$6") (pin "P2") (pinfunction "P1_P2") (pintype "passive"))
    )
    (net (code "72") (name "unconnected-(U$6-S1-PadS2)") (class "Default")
      (node (ref "U$6") (pin "S2") (pinfunction "S1_S2") (pintype "passive"))
    )
    (net (code "73") (name "unconnected-(U$8-P1-PadP2)") (class "Default")
      (node (ref "U$8") (pin "P2") (pinfunction "P1_P2") (pintype "passive"))
    )
    (net (code "74") (name "unconnected-(U$8-S1-PadS2)") (class "Default")
      (node (ref "U$8") (pin "S2") (pinfunction "S1_S2") (pintype "passive"))
    )
    (net (code "75") (name "unconnected-(U$10-P1-PadP2)") (class "Default")
      (node (ref "U$10") (pin "P2") (pinfunction "P1_P2") (pintype "passive"))
    )
    (net (code "76") (name "unconnected-(U$10-S1-PadS2)") (class "Default")
      (node (ref "U$10") (pin "S2") (pinfunction "S1_S2") (pintype "passive"))
    )
    (net (code "77") (name "unconnected-(U$11-P1-PadP2)") (class "Default")
      (node (ref "U$11") (pin "P2") (pinfunction "P1_P2") (pintype "passive"))
    )
    (net (code "78") (name "unconnected-(U$11-S1-PadS2)") (class "Default")
      (node (ref "U$11") (pin "S2") (pinfunction "S1_S2") (pintype "passive"))
    )
    (net (code "79") (name "unconnected-(U$12-P1-PadP2)") (class "Default")
      (node (ref "U$12") (pin "P2") (pinfunction "P1_P2") (pintype "passive"))
    )
    (net (code "80") (name "unconnected-(U$12-S1-PadS2)") (class "Default")
      (node (ref "U$12") (pin "S2") (pinfunction "S1_S2") (pintype "passive"))
    )
    (net (code "81") (name "unconnected-(U$13-P1-PadP2)") (class "Default")
      (node (ref "U$13") (pin "P2") (pinfunction "P1_P2") (pintype "passive"))
    )
    (net (code "82") (name "unconnected-(U$13-S1-PadS2)") (class "Default")
      (node (ref "U$13") (pin "S2") (pinfunction "S1_S2") (pintype "passive"))
    )
  )
)
